# AVRUSB.net
KiCad netlist of a schematic drawn in EAGLE
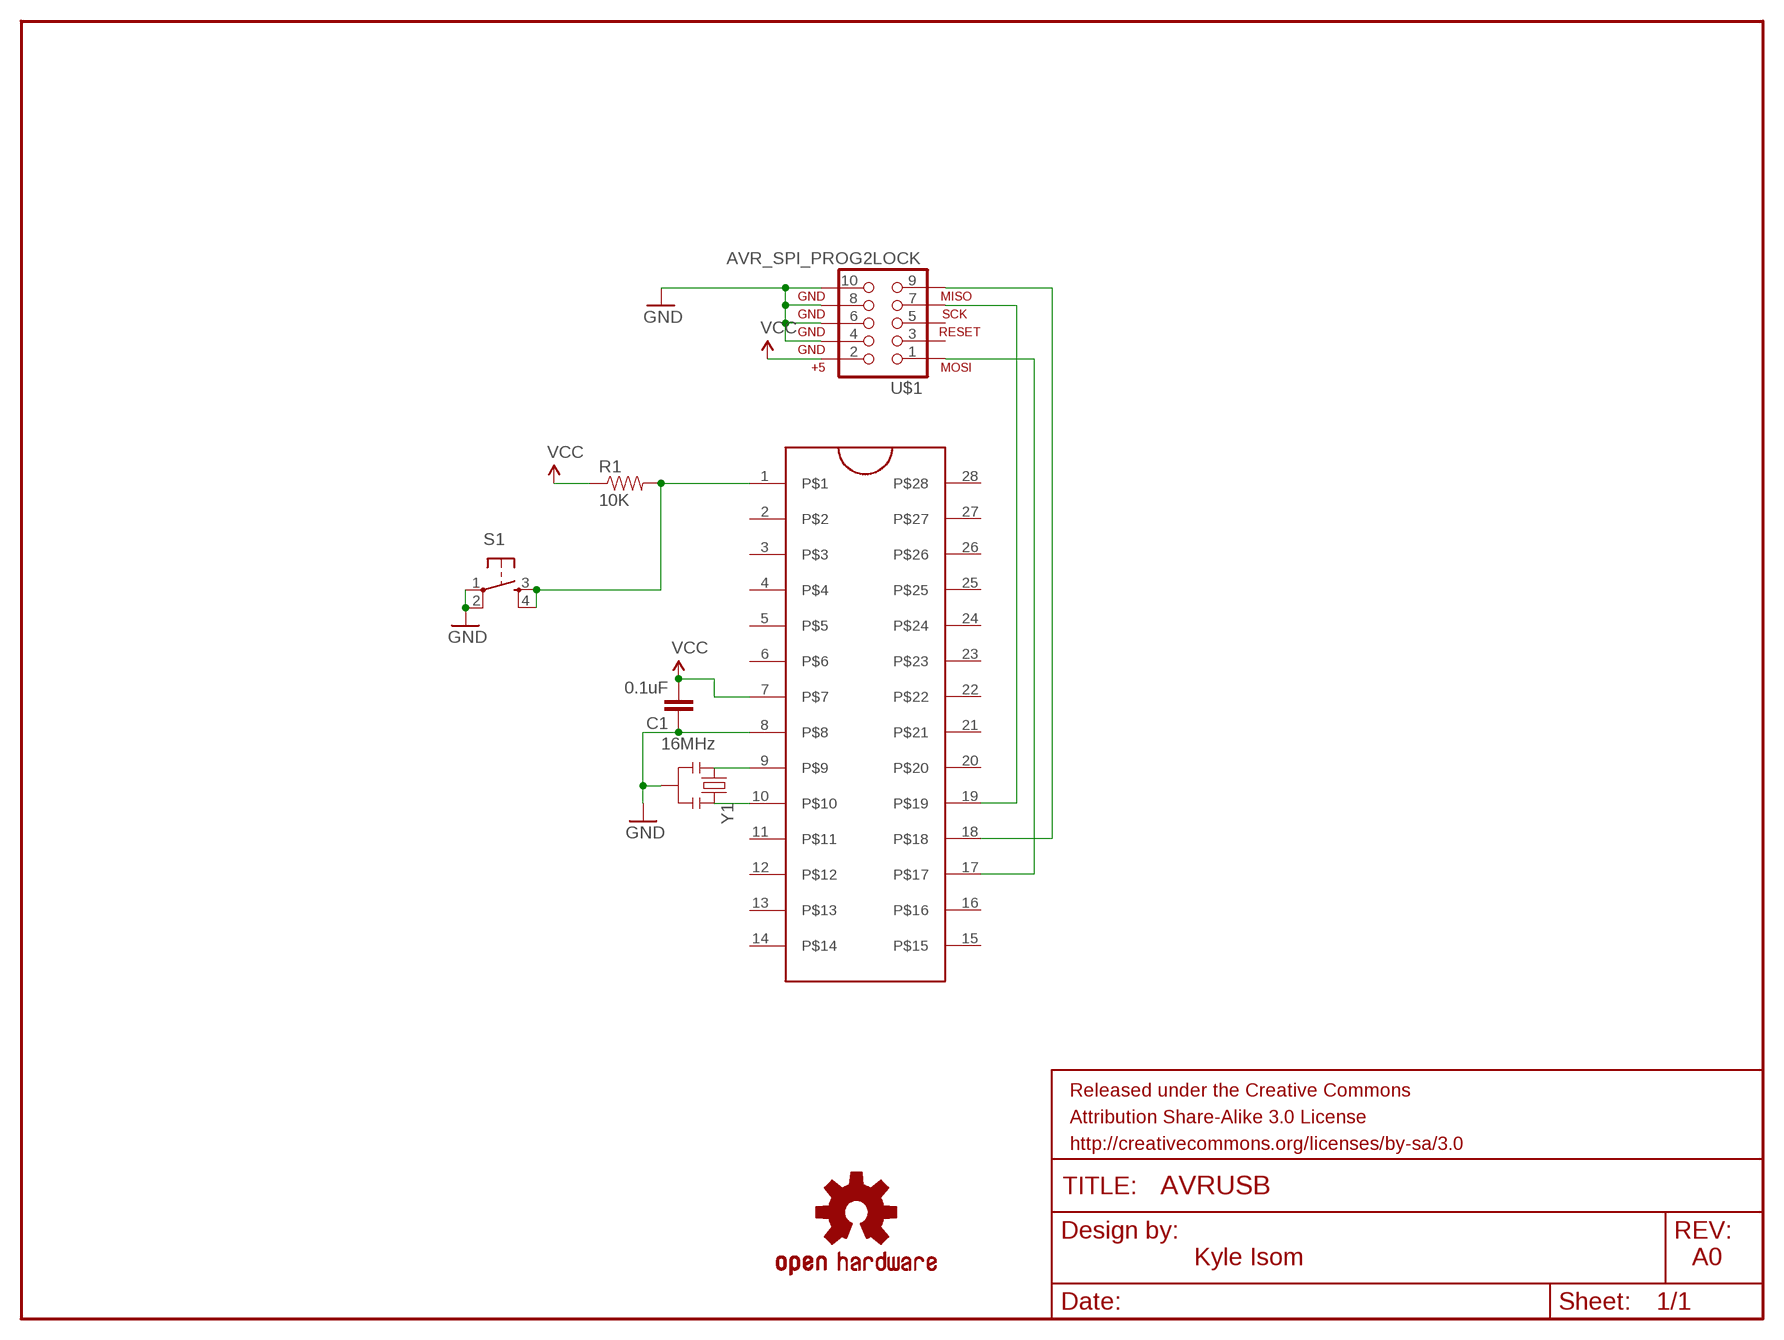
[diagram p0: schematic, sheet 1]

(export (version "E")
  (design (tool "Eeschema 10.0.6"))
  (components
    (comp (ref "C1")
      (value "0.1uF")
      (footprint "eagle-import:CAP-PTH-SMALL")
      (libsource (lib "eagle-import") (part "CAPPTH"))
    )
    (comp (ref "FRAME1")
      (value "FRAME-LETTER")
      (footprint "eagle-import:CREATIVE_COMMONS")
      (libsource (lib "eagle-import") (part "FRAME-LETTER"))
    )
    (comp (ref "LOGO1")
      (value "OSHW-LOGOM")
      (footprint "eagle-import:OSHW-LOGO-M")
      (libsource (lib "eagle-import") (part "OSHW-LOGOM"))
    )
    (comp (ref "R1")
      (value "10K")
      (footprint "eagle-import:AXIAL-0.4")
      (libsource (lib "eagle-import") (part "RESISTORPTH-1/4W"))
    )
    (comp (ref "S1")
      (value "TAC_SWITCHPTH")
      (footprint "eagle-import:TACTILE-PTH")
      (libsource (lib "eagle-import") (part "TAC_SWITCHPTH"))
    )
    (comp (ref "U$1")
      (value "AVR_SPI_PROG2LOCK")
      (footprint "eagle-import:2X5-SHROUDED_LOCK")
      (libsource (lib "eagle-import") (part "AVR_SPI_PROG2LOCK"))
    )
    (comp (ref "U$2")
      (value "ZIFSOCKET-28-3ZIFFSOCKET-28-3")
      (footprint "eagle-import:DIL28-3-ZIF_SOCKET")
      (libsource (lib "eagle-import") (part "ZIFSOCKET-28-3ZIFFSOCKET-28-3"))
    )
    (comp (ref "Y1")
      (value "16MHz")
      (footprint "eagle-import:RESONATOR-PTH")
      (libsource (lib "eagle-import") (part "RESONATORPTH"))
    )
  )
  (nets
    (net (code "1") (name "GND") (class "Default")
      (node (ref "C1") (pin "1") (pinfunction "1_1") (pintype "passive"))
      (node (ref "S1") (pin "1") (pinfunction "1_1") (pintype "passive"))
      (node (ref "S1") (pin "2") (pinfunction "2_2") (pintype "passive"))
      (node (ref "U$1") (pin "10") (pinfunction "10_10") (pintype "passive"))
      (node (ref "U$1") (pin "4") (pinfunction "4_4") (pintype "passive"))
      (node (ref "U$1") (pin "6") (pinfunction "6_6") (pintype "passive"))
      (node (ref "U$1") (pin "8") (pinfunction "8_8") (pintype "passive"))
      (node (ref "U$2") (pin "8") (pinfunction "P$8_8") (pintype "bidirectional"))
      (node (ref "Y1") (pin "2") (pinfunction "2_2") (pintype "passive"))
    )
    (net (code "2") (name "Net-(R1-2)") (class "Default")
      (node (ref "R1") (pin "P$2") (pinfunction "2_P$2") (pintype "passive"))
      (node (ref "S1") (pin "3") (pinfunction "3_3") (pintype "passive"))
      (node (ref "S1") (pin "4") (pinfunction "4_4") (pintype "passive"))
      (node (ref "U$2") (pin "1") (pinfunction "P$1_1") (pintype "bidirectional"))
    )
    (net (code "3") (name "Net-(U$2-P$9)") (class "Default")
      (node (ref "U$2") (pin "9") (pinfunction "P$9_9") (pintype "bidirectional"))
      (node (ref "Y1") (pin "1") (pinfunction "1_1") (pintype "passive"))
    )
    (net (code "4") (name "Net-(U$2-P$10)") (class "Default")
      (node (ref "U$2") (pin "10") (pinfunction "P$10_10") (pintype "bidirectional"))
      (node (ref "Y1") (pin "3") (pinfunction "3_3") (pintype "passive"))
    )
    (net (code "5") (name "Net-(U$2-P$17)") (class "Default")
      (node (ref "U$1") (pin "1") (pinfunction "1_1") (pintype "passive"))
      (node (ref "U$2") (pin "17") (pinfunction "P$17_17") (pintype "bidirectional"))
    )
    (net (code "6") (name "Net-(U$2-P$18)") (class "Default")
      (node (ref "U$1") (pin "9") (pinfunction "9_9") (pintype "passive"))
      (node (ref "U$2") (pin "18") (pinfunction "P$18_18") (pintype "bidirectional"))
    )
    (net (code "7") (name "Net-(U$2-P$19)") (class "Default")
      (node (ref "U$1") (pin "7") (pinfunction "7_7") (pintype "passive"))
      (node (ref "U$2") (pin "19") (pinfunction "P$19_19") (pintype "bidirectional"))
    )
    (net (code "8") (name "VCC") (class "Default")
      (node (ref "C1") (pin "2") (pinfunction "2_2") (pintype "passive"))
      (node (ref "R1") (pin "P$1") (pinfunction "1_P$1") (pintype "passive"))
      (node (ref "U$1") (pin "2") (pinfunction "2_2") (pintype "passive"))
      (node (ref "U$2") (pin "7") (pinfunction "P$7_7") (pintype "bidirectional"))
    )
    (net (code "9") (name "unconnected-(U$1-Pad3)") (class "Default")
      (node (ref "U$1") (pin "3") (pinfunction "3_3") (pintype "passive"))
    )
    (net (code "10") (name "unconnected-(U$1-Pad5)") (class "Default")
      (node (ref "U$1") (pin "5") (pinfunction "5_5") (pintype "passive"))
    )
    (net (code "11") (name "unconnected-(U$2-P$2-Pad2)") (class "Default")
      (node (ref "U$2") (pin "2") (pinfunction "P$2_2") (pintype "bidirectional"))
    )
    (net (code "12") (name "unconnected-(U$2-P$3-Pad3)") (class "Default")
      (node (ref "U$2") (pin "3") (pinfunction "P$3_3") (pintype "bidirectional"))
    )
    (net (code "13") (name "unconnected-(U$2-P$4-Pad4)") (class "Default")
      (node (ref "U$2") (pin "4") (pinfunction "P$4_4") (pintype "bidirectional"))
    )
    (net (code "14") (name "unconnected-(U$2-P$5-Pad5)") (class "Default")
      (node (ref "U$2") (pin "5") (pinfunction "P$5_5") (pintype "bidirectional"))
    )
    (net (code "15") (name "unconnected-(U$2-P$6-Pad6)") (class "Default")
      (node (ref "U$2") (pin "6") (pinfunction "P$6_6") (pintype "bidirectional"))
    )
    (net (code "16") (name "unconnected-(U$2-P$11-Pad11)") (class "Default")
      (node (ref "U$2") (pin "11") (pinfunction "P$11_11") (pintype "bidirectional"))
    )
    (net (code "17") (name "unconnected-(U$2-P$12-Pad12)") (class "Default")
      (node (ref "U$2") (pin "12") (pinfunction "P$12_12") (pintype "bidirectional"))
    )
    (net (code "18") (name "unconnected-(U$2-P$13-Pad13)") (class "Default")
      (node (ref "U$2") (pin "13") (pinfunction "P$13_13") (pintype "bidirectional"))
    )
    (net (code "19") (name "unconnected-(U$2-P$14-Pad14)") (class "Default")
      (node (ref "U$2") (pin "14") (pinfunction "P$14_14") (pintype "bidirectional"))
    )
    (net (code "20") (name "unconnected-(U$2-P$15-Pad15)") (class "Default")
      (node (ref "U$2") (pin "15") (pinfunction "P$15_15") (pintype "bidirectional"))
    )
    (net (code "21") (name "unconnected-(U$2-P$16-Pad16)") (class "Default")
      (node (ref "U$2") (pin "16") (pinfunction "P$16_16") (pintype "bidirectional"))
    )
    (net (code "22") (name "unconnected-(U$2-P$20-Pad20)") (class "Default")
      (node (ref "U$2") (pin "20") (pinfunction "P$20_20") (pintype "bidirectional"))
    )
    (net (code "23") (name "unconnected-(U$2-P$21-Pad21)") (class "Default")
      (node (ref "U$2") (pin "21") (pinfunction "P$21_21") (pintype "bidirectional"))
    )
    (net (code "24") (name "unconnected-(U$2-P$22-Pad22)") (class "Default")
      (node (ref "U$2") (pin "22") (pinfunction "P$22_22") (pintype "bidirectional"))
    )
    (net (code "25") (name "unconnected-(U$2-P$23-Pad23)") (class "Default")
      (node (ref "U$2") (pin "23") (pinfunction "P$23_23") (pintype "bidirectional"))
    )
    (net (code "26") (name "unconnected-(U$2-P$24-Pad24)") (class "Default")
      (node (ref "U$2") (pin "24") (pinfunction "P$24_24") (pintype "bidirectional"))
    )
    (net (code "27") (name "unconnected-(U$2-P$25-Pad25)") (class "Default")
      (node (ref "U$2") (pin "25") (pinfunction "P$25_25") (pintype "bidirectional"))
    )
    (net (code "28") (name "unconnected-(U$2-P$26-Pad26)") (class "Default")
      (node (ref "U$2") (pin "26") (pinfunction "P$26_26") (pintype "bidirectional"))
    )
    (net (code "29") (name "unconnected-(U$2-P$27-Pad27)") (class "Default")
      (node (ref "U$2") (pin "27") (pinfunction "P$27_27") (pintype "bidirectional"))
    )
    (net (code "30") (name "unconnected-(U$2-P$28-Pad28)") (class "Default")
      (node (ref "U$2") (pin "28") (pinfunction "P$28_28") (pintype "bidirectional"))
    )
  )
)
